# TCAN337_CANbus_Transciever.net
KiCad netlist of a schematic drawn in Altium Designer
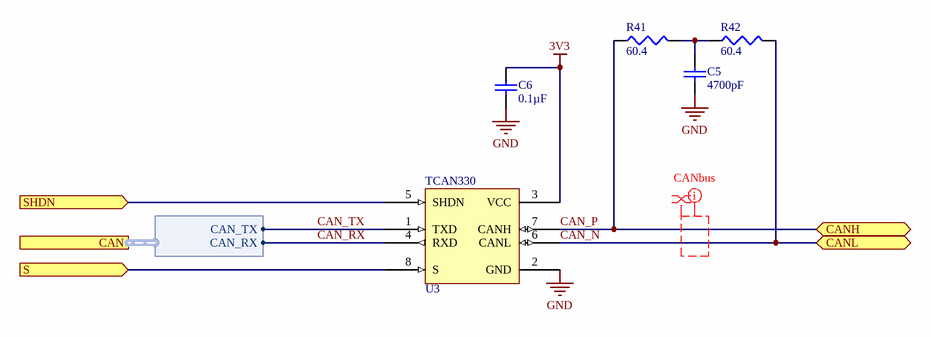
[diagram p0: TCAN337 CANbus Transciever.SchDoc]

(export (version "E")
  (design (tool "Eeschema 10.0.6"))
  (components
    (comp (ref "C5")
      (value "4700pF")
      (footprint "TDK-CGA2B")
      (description "CAP CER 4700PF 50V X8R 0402")
      (fields
        (field (name "PART NUMBER") "PC-TDK-01714")
        (field (name "MANUFACTURER PART NUMBER") "CGA2B2X8R1H472K050BA")
        (field (name "PUBLISHER") "AlbertaSat")
      )
      (libsource (lib "Database") (part "Cap"))
    )
    (comp (ref "C6")
      (value "0.1µF")
      (footprint "TDK-CGA2B")
      (description "CAP CER 0.1UF 50V X7R 0402")
      (fields
        (field (name "PART NUMBER") "PC-TDK-02259")
        (field (name "MANUFACTURER PART NUMBER") "CGA2B3X7R1H104K050BB")
        (field (name "PUBLISHER") "AlbertaSat")
      )
      (libsource (lib "Database") (part "Cap"))
    )
    (comp (ref "R41")
      (value "60.4")
      (footprint "PANA-ERA2A")
      (description "RES SMD 60.4 OHM 0.1% 1/16W 0402")
      (fields
        (field (name "PART NUMBER") "13829")
        (field (name "MANUFACTURER PART NUMBER") "ERA-2AEB60R4X")
        (field (name "PUBLISHER") "Altium Limited")
      )
      (libsource (lib "Database") (part "Res3"))
    )
    (comp (ref "R42")
      (value "60.4")
      (footprint "PANA-ERA2A")
      (description "RES SMD 60.4 OHM 0.1% 1/16W 0402")
      (fields
        (field (name "PART NUMBER") "13829")
        (field (name "MANUFACTURER PART NUMBER") "ERA-2AEB60R4X")
        (field (name "PUBLISHER") "Altium Limited")
      )
      (libsource (lib "Database") (part "Res3"))
    )
    (comp (ref "U3")
      (value "TCAN330")
      (footprint "TI-R-PDSO-G8")
      (description "IC TRANSCEIVER 1/1 SOT23-8")
      (fields (field (name "PART NUMBER") "165") (field (name "MANUFACTURER PART NUMBER") "TCAN337GDCNR"))
      (libsource (lib "Database") (part "TCAN330"))
    )
  )
  (nets
    (net (code "2") (name "/CAN_N") (class "Default")
      (node (ref "R42") (pin "2") (pinfunction "2_2") (pintype "passive"))
      (node (ref "U3") (pin "6") (pinfunction "CANL_6") (pintype "bidirectional"))
    )
    (net (code "3") (name "/CAN_P") (class "Default")
      (node (ref "R41") (pin "1") (pinfunction "1_1") (pintype "passive"))
      (node (ref "U3") (pin "7") (pinfunction "CANH_7") (pintype "bidirectional"))
    )
    (net (code "4") (name "/CAN_RX") (class "Default")
      (node (ref "U3") (pin "4") (pinfunction "RXD_4") (pintype "output"))
    )
    (net (code "5") (name "/CAN_TX") (class "Default")
      (node (ref "U3") (pin "1") (pinfunction "TXD_1") (pintype "input"))
    )
    (net (code "6") (name "/S") (class "Default")
      (node (ref "U3") (pin "8") (pinfunction "S_8") (pintype "input"))
    )
    (net (code "7") (name "/SHDN") (class "Default")
      (node (ref "U3") (pin "5") (pinfunction "SHDN_5") (pintype "input"))
    )
    (net (code "9") (name "3V3") (class "Default")
      (node (ref "C6") (pin "1") (pinfunction "1_1") (pintype "passive"))
      (node (ref "U3") (pin "3") (pinfunction "VCC_3") (pintype "power_in"))
    )
    (net (code "10") (name "GND") (class "Default")
      (node (ref "C5") (pin "1") (pinfunction "1_1") (pintype "passive"))
      (node (ref "C6") (pin "2") (pinfunction "2_2") (pintype "passive"))
      (node (ref "U3") (pin "2") (pinfunction "GND_2") (pintype "power_in"))
    )
    (net (code "11") (name "Net-(C5-Pad2)") (class "Default")
      (node (ref "C5") (pin "2") (pinfunction "2_2") (pintype "passive"))
      (node (ref "R41") (pin "2") (pinfunction "2_2") (pintype "passive"))
      (node (ref "R42") (pin "1") (pinfunction "1_1") (pintype "passive"))
    )
  )
)
